# Driver_Adapter.net
KiCad netlist of a schematic drawn in EAGLE
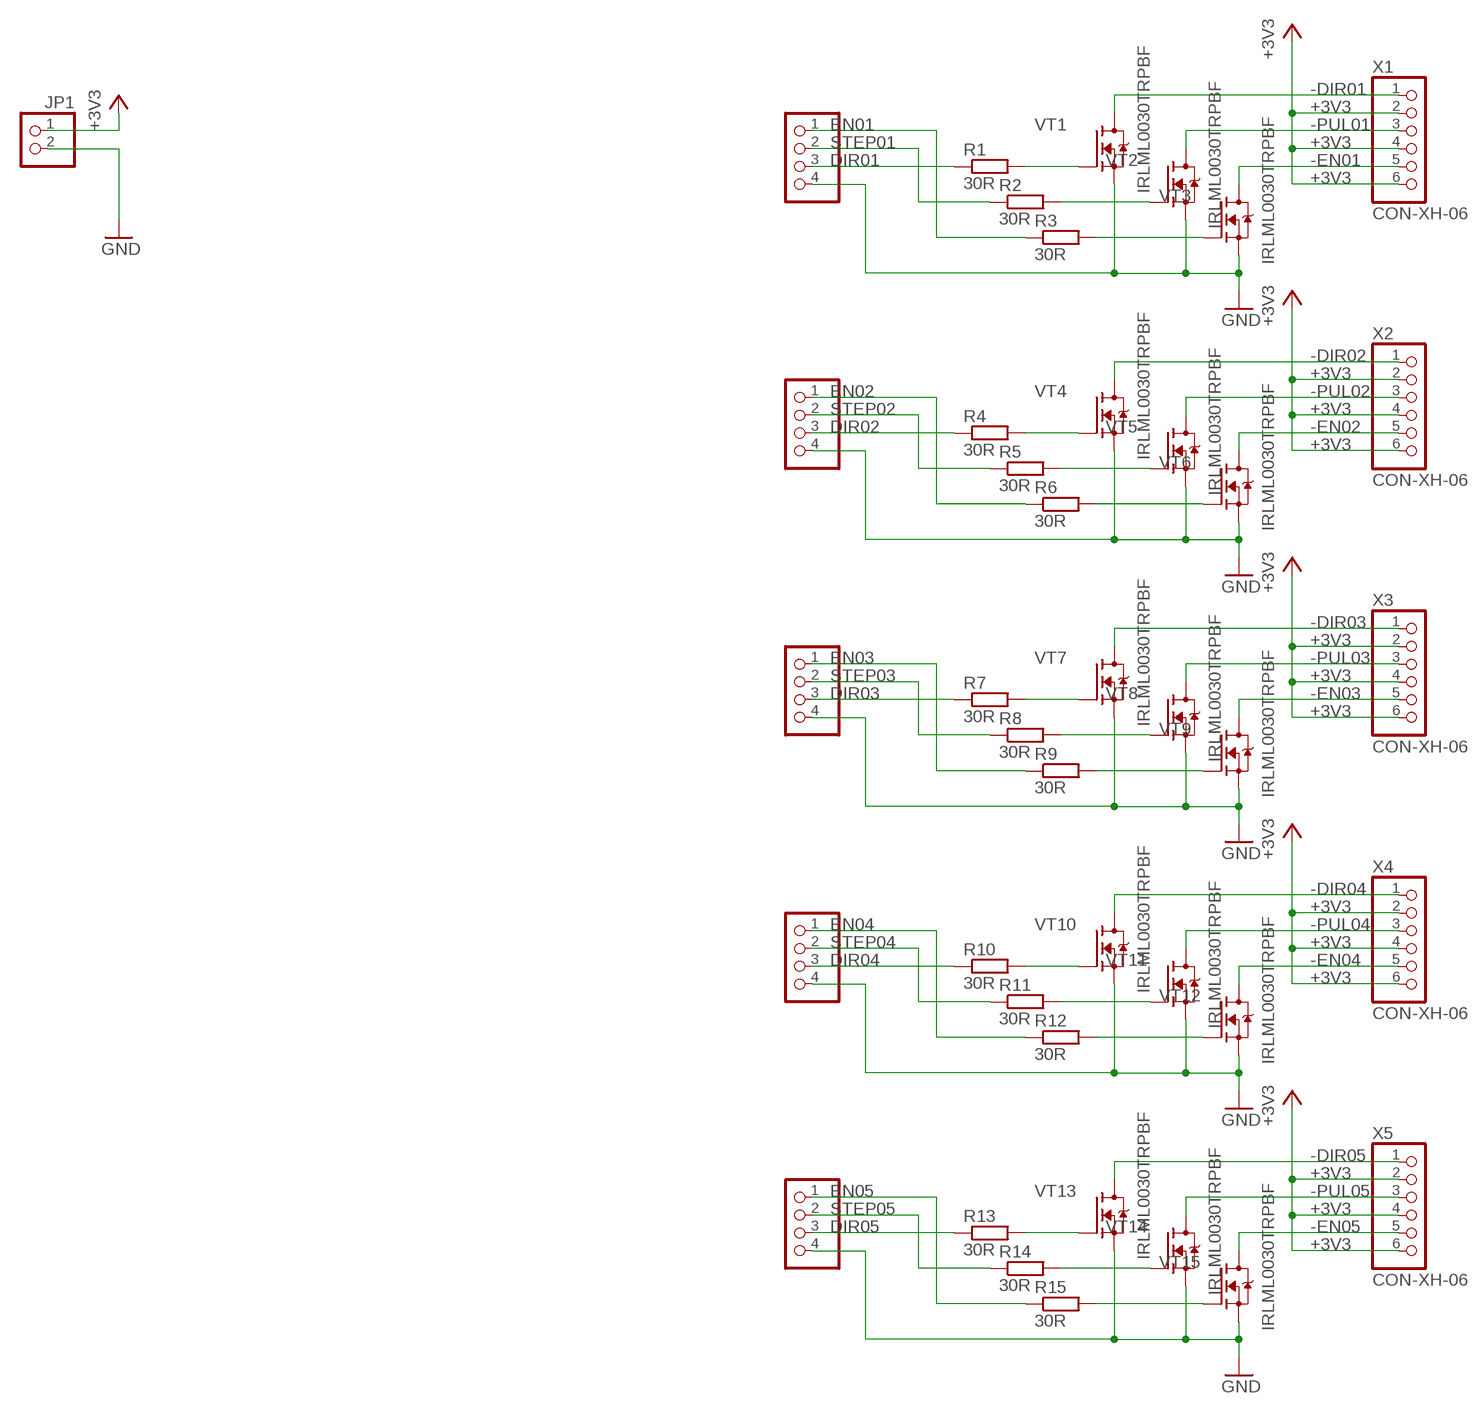
[diagram p0: schematic, sheet 1]

(export (version "E")
  (design (tool "Eeschema 10.0.6"))
  (components
    (comp (ref "JP1")
      (value "PINHD-1X2")
      (footprint "eagle-import:1X02")
      (libsource (lib "eagle-import") (part "PINHD-1X2"))
    )
    (comp (ref "JP2")
      (value "PINHD-1X4")
      (footprint "eagle-import:1X04")
      (libsource (lib "eagle-import") (part "PINHD-1X4"))
    )
    (comp (ref "JP3")
      (value "PINHD-1X4")
      (footprint "eagle-import:1X04")
      (libsource (lib "eagle-import") (part "PINHD-1X4"))
    )
    (comp (ref "JP4")
      (value "PINHD-1X4")
      (footprint "eagle-import:1X04")
      (libsource (lib "eagle-import") (part "PINHD-1X4"))
    )
    (comp (ref "JP5")
      (value "PINHD-1X4")
      (footprint "eagle-import:1X04")
      (libsource (lib "eagle-import") (part "PINHD-1X4"))
    )
    (comp (ref "JP6")
      (value "PINHD-1X4")
      (footprint "eagle-import:1X04")
      (libsource (lib "eagle-import") (part "PINHD-1X4"))
    )
    (comp (ref "R1")
      (value "30R")
      (footprint "eagle-import:RESC3216X60")
      (libsource (lib "eagle-import") (part "R_R1206"))
    )
    (comp (ref "R2")
      (value "30R")
      (footprint "eagle-import:RESC3216X60")
      (libsource (lib "eagle-import") (part "R_R1206"))
    )
    (comp (ref "R3")
      (value "30R")
      (footprint "eagle-import:RESC3216X60")
      (libsource (lib "eagle-import") (part "R_R1206"))
    )
    (comp (ref "R4")
      (value "30R")
      (footprint "eagle-import:RESC3216X60")
      (libsource (lib "eagle-import") (part "R_R1206"))
    )
    (comp (ref "R5")
      (value "30R")
      (footprint "eagle-import:RESC3216X60")
      (libsource (lib "eagle-import") (part "R_R1206"))
    )
    (comp (ref "R6")
      (value "30R")
      (footprint "eagle-import:RESC3216X60")
      (libsource (lib "eagle-import") (part "R_R1206"))
    )
    (comp (ref "R7")
      (value "30R")
      (footprint "eagle-import:RESC3216X60")
      (libsource (lib "eagle-import") (part "R_R1206"))
    )
    (comp (ref "R8")
      (value "30R")
      (footprint "eagle-import:RESC3216X60")
      (libsource (lib "eagle-import") (part "R_R1206"))
    )
    (comp (ref "R9")
      (value "30R")
      (footprint "eagle-import:RESC3216X60")
      (libsource (lib "eagle-import") (part "R_R1206"))
    )
    (comp (ref "R10")
      (value "30R")
      (footprint "eagle-import:RESC3216X60")
      (libsource (lib "eagle-import") (part "R_R1206"))
    )
    (comp (ref "R11")
      (value "30R")
      (footprint "eagle-import:RESC3216X60")
      (libsource (lib "eagle-import") (part "R_R1206"))
    )
    (comp (ref "R12")
      (value "30R")
      (footprint "eagle-import:RESC3216X60")
      (libsource (lib "eagle-import") (part "R_R1206"))
    )
    (comp (ref "R13")
      (value "30R")
      (footprint "eagle-import:RESC3216X60")
      (libsource (lib "eagle-import") (part "R_R1206"))
    )
    (comp (ref "R14")
      (value "30R")
      (footprint "eagle-import:RESC3216X60")
      (libsource (lib "eagle-import") (part "R_R1206"))
    )
    (comp (ref "R15")
      (value "30R")
      (footprint "eagle-import:RESC3216X60")
      (libsource (lib "eagle-import") (part "R_R1206"))
    )
    (comp (ref "VT1")
      (value "IRLML0030TRPBF")
      (footprint "eagle-import:SOT95P240X115-3")
      (libsource (lib "eagle-import") (part "FET-NSOT-23"))
    )
    (comp (ref "VT2")
      (value "IRLML0030TRPBF")
      (footprint "eagle-import:SOT95P240X115-3")
      (libsource (lib "eagle-import") (part "FET-NSOT-23"))
    )
    (comp (ref "VT3")
      (value "IRLML0030TRPBF")
      (footprint "eagle-import:SOT95P240X115-3")
      (libsource (lib "eagle-import") (part "FET-NSOT-23"))
    )
    (comp (ref "VT4")
      (value "IRLML0030TRPBF")
      (footprint "eagle-import:SOT95P240X115-3")
      (libsource (lib "eagle-import") (part "FET-NSOT-23"))
    )
    (comp (ref "VT5")
      (value "IRLML0030TRPBF")
      (footprint "eagle-import:SOT95P240X115-3")
      (libsource (lib "eagle-import") (part "FET-NSOT-23"))
    )
    (comp (ref "VT6")
      (value "IRLML0030TRPBF")
      (footprint "eagle-import:SOT95P240X115-3")
      (libsource (lib "eagle-import") (part "FET-NSOT-23"))
    )
    (comp (ref "VT7")
      (value "IRLML0030TRPBF")
      (footprint "eagle-import:SOT95P240X115-3")
      (libsource (lib "eagle-import") (part "FET-NSOT-23"))
    )
    (comp (ref "VT8")
      (value "IRLML0030TRPBF")
      (footprint "eagle-import:SOT95P240X115-3")
      (libsource (lib "eagle-import") (part "FET-NSOT-23"))
    )
    (comp (ref "VT9")
      (value "IRLML0030TRPBF")
      (footprint "eagle-import:SOT95P240X115-3")
      (libsource (lib "eagle-import") (part "FET-NSOT-23"))
    )
    (comp (ref "VT10")
      (value "IRLML0030TRPBF")
      (footprint "eagle-import:SOT95P240X115-3")
      (libsource (lib "eagle-import") (part "FET-NSOT-23"))
    )
    (comp (ref "VT11")
      (value "IRLML0030TRPBF")
      (footprint "eagle-import:SOT95P240X115-3")
      (libsource (lib "eagle-import") (part "FET-NSOT-23"))
    )
    (comp (ref "VT12")
      (value "IRLML0030TRPBF")
      (footprint "eagle-import:SOT95P240X115-3")
      (libsource (lib "eagle-import") (part "FET-NSOT-23"))
    )
    (comp (ref "VT13")
      (value "IRLML0030TRPBF")
      (footprint "eagle-import:SOT95P240X115-3")
      (libsource (lib "eagle-import") (part "FET-NSOT-23"))
    )
    (comp (ref "VT14")
      (value "IRLML0030TRPBF")
      (footprint "eagle-import:SOT95P240X115-3")
      (libsource (lib "eagle-import") (part "FET-NSOT-23"))
    )
    (comp (ref "VT15")
      (value "IRLML0030TRPBF")
      (footprint "eagle-import:SOT95P240X115-3")
      (libsource (lib "eagle-import") (part "FET-NSOT-23"))
    )
    (comp (ref "X1")
      (value "CON-XH-06")
      (footprint "eagle-import:XH-06")
      (libsource (lib "eagle-import") (part "CON-XH-06"))
    )
    (comp (ref "X2")
      (value "CON-XH-06")
      (footprint "eagle-import:XH-06")
      (libsource (lib "eagle-import") (part "CON-XH-06"))
    )
    (comp (ref "X3")
      (value "CON-XH-06")
      (footprint "eagle-import:XH-06")
      (libsource (lib "eagle-import") (part "CON-XH-06"))
    )
    (comp (ref "X4")
      (value "CON-XH-06")
      (footprint "eagle-import:XH-06")
      (libsource (lib "eagle-import") (part "CON-XH-06"))
    )
    (comp (ref "X5")
      (value "CON-XH-06")
      (footprint "eagle-import:XH-06")
      (libsource (lib "eagle-import") (part "CON-XH-06"))
    )
  )
  (nets
    (net (code "1") (name "+3V3") (class "Default")
      (node (ref "JP1") (pin "1") (pinfunction "1_1") (pintype "passive"))
      (node (ref "X1") (pin "2") (pinfunction "2_2") (pintype "passive"))
      (node (ref "X1") (pin "4") (pinfunction "4_4") (pintype "passive"))
      (node (ref "X1") (pin "6") (pinfunction "6_6") (pintype "passive"))
      (node (ref "X2") (pin "2") (pinfunction "2_2") (pintype "passive"))
      (node (ref "X2") (pin "4") (pinfunction "4_4") (pintype "passive"))
      (node (ref "X2") (pin "6") (pinfunction "6_6") (pintype "passive"))
      (node (ref "X3") (pin "2") (pinfunction "2_2") (pintype "passive"))
      (node (ref "X3") (pin "4") (pinfunction "4_4") (pintype "passive"))
      (node (ref "X3") (pin "6") (pinfunction "6_6") (pintype "passive"))
      (node (ref "X4") (pin "2") (pinfunction "2_2") (pintype "passive"))
      (node (ref "X4") (pin "4") (pinfunction "4_4") (pintype "passive"))
      (node (ref "X4") (pin "6") (pinfunction "6_6") (pintype "passive"))
      (node (ref "X5") (pin "2") (pinfunction "2_2") (pintype "passive"))
      (node (ref "X5") (pin "4") (pinfunction "4_4") (pintype "passive"))
      (node (ref "X5") (pin "6") (pinfunction "6_6") (pintype "passive"))
    )
    (net (code "2") (name "/-DIR01") (class "Default")
      (node (ref "VT1") (pin "3") (pinfunction "D_3") (pintype "passive"))
      (node (ref "X1") (pin "1") (pinfunction "1_1") (pintype "passive"))
    )
    (net (code "3") (name "/-DIR02") (class "Default")
      (node (ref "VT4") (pin "3") (pinfunction "D_3") (pintype "passive"))
      (node (ref "X2") (pin "1") (pinfunction "1_1") (pintype "passive"))
    )
    (net (code "4") (name "/-DIR03") (class "Default")
      (node (ref "VT7") (pin "3") (pinfunction "D_3") (pintype "passive"))
      (node (ref "X3") (pin "1") (pinfunction "1_1") (pintype "passive"))
    )
    (net (code "5") (name "/-DIR04") (class "Default")
      (node (ref "VT10") (pin "3") (pinfunction "D_3") (pintype "passive"))
      (node (ref "X4") (pin "1") (pinfunction "1_1") (pintype "passive"))
    )
    (net (code "6") (name "/-DIR05") (class "Default")
      (node (ref "VT13") (pin "3") (pinfunction "D_3") (pintype "passive"))
      (node (ref "X5") (pin "1") (pinfunction "1_1") (pintype "passive"))
    )
    (net (code "7") (name "/-EN01") (class "Default")
      (node (ref "VT3") (pin "3") (pinfunction "D_3") (pintype "passive"))
      (node (ref "X1") (pin "5") (pinfunction "5_5") (pintype "passive"))
    )
    (net (code "8") (name "/-EN02") (class "Default")
      (node (ref "VT6") (pin "3") (pinfunction "D_3") (pintype "passive"))
      (node (ref "X2") (pin "5") (pinfunction "5_5") (pintype "passive"))
    )
    (net (code "9") (name "/-EN03") (class "Default")
      (node (ref "VT9") (pin "3") (pinfunction "D_3") (pintype "passive"))
      (node (ref "X3") (pin "5") (pinfunction "5_5") (pintype "passive"))
    )
    (net (code "10") (name "/-EN04") (class "Default")
      (node (ref "VT12") (pin "3") (pinfunction "D_3") (pintype "passive"))
      (node (ref "X4") (pin "5") (pinfunction "5_5") (pintype "passive"))
    )
    (net (code "11") (name "/-EN05") (class "Default")
      (node (ref "VT15") (pin "3") (pinfunction "D_3") (pintype "passive"))
      (node (ref "X5") (pin "5") (pinfunction "5_5") (pintype "passive"))
    )
    (net (code "12") (name "/-PUL01") (class "Default")
      (node (ref "VT2") (pin "3") (pinfunction "D_3") (pintype "passive"))
      (node (ref "X1") (pin "3") (pinfunction "3_3") (pintype "passive"))
    )
    (net (code "13") (name "/-PUL02") (class "Default")
      (node (ref "VT5") (pin "3") (pinfunction "D_3") (pintype "passive"))
      (node (ref "X2") (pin "3") (pinfunction "3_3") (pintype "passive"))
    )
    (net (code "14") (name "/-PUL03") (class "Default")
      (node (ref "VT8") (pin "3") (pinfunction "D_3") (pintype "passive"))
      (node (ref "X3") (pin "3") (pinfunction "3_3") (pintype "passive"))
    )
    (net (code "15") (name "/-PUL04") (class "Default")
      (node (ref "VT11") (pin "3") (pinfunction "D_3") (pintype "passive"))
      (node (ref "X4") (pin "3") (pinfunction "3_3") (pintype "passive"))
    )
    (net (code "16") (name "/-PUL05") (class "Default")
      (node (ref "VT14") (pin "3") (pinfunction "D_3") (pintype "passive"))
      (node (ref "X5") (pin "3") (pinfunction "3_3") (pintype "passive"))
    )
    (net (code "17") (name "/DIR01") (class "Default")
      (node (ref "JP2") (pin "3") (pinfunction "3_3") (pintype "passive"))
      (node (ref "R1") (pin "1") (pinfunction "1_1") (pintype "passive"))
    )
    (net (code "18") (name "/DIR02") (class "Default")
      (node (ref "JP3") (pin "3") (pinfunction "3_3") (pintype "passive"))
      (node (ref "R4") (pin "1") (pinfunction "1_1") (pintype "passive"))
    )
    (net (code "19") (name "/DIR03") (class "Default")
      (node (ref "JP4") (pin "3") (pinfunction "3_3") (pintype "passive"))
      (node (ref "R7") (pin "1") (pinfunction "1_1") (pintype "passive"))
    )
    (net (code "20") (name "/DIR04") (class "Default")
      (node (ref "JP5") (pin "3") (pinfunction "3_3") (pintype "passive"))
      (node (ref "R10") (pin "1") (pinfunction "1_1") (pintype "passive"))
    )
    (net (code "21") (name "/DIR05") (class "Default")
      (node (ref "JP6") (pin "3") (pinfunction "3_3") (pintype "passive"))
      (node (ref "R13") (pin "1") (pinfunction "1_1") (pintype "passive"))
    )
    (net (code "22") (name "/EN01") (class "Default")
      (node (ref "JP2") (pin "1") (pinfunction "1_1") (pintype "passive"))
      (node (ref "R3") (pin "1") (pinfunction "1_1") (pintype "passive"))
    )
    (net (code "23") (name "/EN02") (class "Default")
      (node (ref "JP3") (pin "1") (pinfunction "1_1") (pintype "passive"))
      (node (ref "R6") (pin "1") (pinfunction "1_1") (pintype "passive"))
    )
    (net (code "24") (name "/EN03") (class "Default")
      (node (ref "JP4") (pin "1") (pinfunction "1_1") (pintype "passive"))
      (node (ref "R9") (pin "1") (pinfunction "1_1") (pintype "passive"))
    )
    (net (code "25") (name "/EN04") (class "Default")
      (node (ref "JP5") (pin "1") (pinfunction "1_1") (pintype "passive"))
      (node (ref "R12") (pin "1") (pinfunction "1_1") (pintype "passive"))
    )
    (net (code "26") (name "/EN05") (class "Default")
      (node (ref "JP6") (pin "1") (pinfunction "1_1") (pintype "passive"))
      (node (ref "R15") (pin "1") (pinfunction "1_1") (pintype "passive"))
    )
    (net (code "27") (name "/STEP01") (class "Default")
      (node (ref "JP2") (pin "2") (pinfunction "2_2") (pintype "passive"))
      (node (ref "R2") (pin "1") (pinfunction "1_1") (pintype "passive"))
    )
    (net (code "28") (name "/STEP02") (class "Default")
      (node (ref "JP3") (pin "2") (pinfunction "2_2") (pintype "passive"))
      (node (ref "R5") (pin "1") (pinfunction "1_1") (pintype "passive"))
    )
    (net (code "29") (name "/STEP03") (class "Default")
      (node (ref "JP4") (pin "2") (pinfunction "2_2") (pintype "passive"))
      (node (ref "R8") (pin "1") (pinfunction "1_1") (pintype "passive"))
    )
    (net (code "30") (name "/STEP04") (class "Default")
      (node (ref "JP5") (pin "2") (pinfunction "2_2") (pintype "passive"))
      (node (ref "R11") (pin "1") (pinfunction "1_1") (pintype "passive"))
    )
    (net (code "31") (name "/STEP05") (class "Default")
      (node (ref "JP6") (pin "2") (pinfunction "2_2") (pintype "passive"))
      (node (ref "R14") (pin "1") (pinfunction "1_1") (pintype "passive"))
    )
    (net (code "32") (name "GND") (class "Default")
      (node (ref "JP1") (pin "2") (pinfunction "2_2") (pintype "passive"))
      (node (ref "JP2") (pin "4") (pinfunction "4_4") (pintype "passive"))
      (node (ref "JP3") (pin "4") (pinfunction "4_4") (pintype "passive"))
      (node (ref "JP4") (pin "4") (pinfunction "4_4") (pintype "passive"))
      (node (ref "JP5") (pin "4") (pinfunction "4_4") (pintype "passive"))
      (node (ref "JP6") (pin "4") (pinfunction "4_4") (pintype "passive"))
      (node (ref "VT1") (pin "2") (pinfunction "S_2") (pintype "passive"))
      (node (ref "VT10") (pin "2") (pinfunction "S_2") (pintype "passive"))
      (node (ref "VT11") (pin "2") (pinfunction "S_2") (pintype "passive"))
      (node (ref "VT12") (pin "2") (pinfunction "S_2") (pintype "passive"))
      (node (ref "VT13") (pin "2") (pinfunction "S_2") (pintype "passive"))
      (node (ref "VT14") (pin "2") (pinfunction "S_2") (pintype "passive"))
      (node (ref "VT15") (pin "2") (pinfunction "S_2") (pintype "passive"))
      (node (ref "VT2") (pin "2") (pinfunction "S_2") (pintype "passive"))
      (node (ref "VT3") (pin "2") (pinfunction "S_2") (pintype "passive"))
      (node (ref "VT4") (pin "2") (pinfunction "S_2") (pintype "passive"))
      (node (ref "VT5") (pin "2") (pinfunction "S_2") (pintype "passive"))
      (node (ref "VT6") (pin "2") (pinfunction "S_2") (pintype "passive"))
      (node (ref "VT7") (pin "2") (pinfunction "S_2") (pintype "passive"))
      (node (ref "VT8") (pin "2") (pinfunction "S_2") (pintype "passive"))
      (node (ref "VT9") (pin "2") (pinfunction "S_2") (pintype "passive"))
    )
    (net (code "33") (name "Net-(VT1-G)") (class "Default")
      (node (ref "R1") (pin "2") (pinfunction "2_2") (pintype "passive"))
      (node (ref "VT1") (pin "1") (pinfunction "G_1") (pintype "passive"))
    )
    (net (code "34") (name "Net-(VT2-G)") (class "Default")
      (node (ref "R2") (pin "2") (pinfunction "2_2") (pintype "passive"))
      (node (ref "VT2") (pin "1") (pinfunction "G_1") (pintype "passive"))
    )
    (net (code "35") (name "Net-(VT3-G)") (class "Default")
      (node (ref "R3") (pin "2") (pinfunction "2_2") (pintype "passive"))
      (node (ref "VT3") (pin "1") (pinfunction "G_1") (pintype "passive"))
    )
    (net (code "36") (name "Net-(VT4-G)") (class "Default")
      (node (ref "R4") (pin "2") (pinfunction "2_2") (pintype "passive"))
      (node (ref "VT4") (pin "1") (pinfunction "G_1") (pintype "passive"))
    )
    (net (code "37") (name "Net-(VT5-G)") (class "Default")
      (node (ref "R5") (pin "2") (pinfunction "2_2") (pintype "passive"))
      (node (ref "VT5") (pin "1") (pinfunction "G_1") (pintype "passive"))
    )
    (net (code "38") (name "Net-(VT6-G)") (class "Default")
      (node (ref "R6") (pin "2") (pinfunction "2_2") (pintype "passive"))
      (node (ref "VT6") (pin "1") (pinfunction "G_1") (pintype "passive"))
    )
    (net (code "39") (name "Net-(VT7-G)") (class "Default")
      (node (ref "R7") (pin "2") (pinfunction "2_2") (pintype "passive"))
      (node (ref "VT7") (pin "1") (pinfunction "G_1") (pintype "passive"))
    )
    (net (code "40") (name "Net-(VT8-G)") (class "Default")
      (node (ref "R8") (pin "2") (pinfunction "2_2") (pintype "passive"))
      (node (ref "VT8") (pin "1") (pinfunction "G_1") (pintype "passive"))
    )
    (net (code "41") (name "Net-(VT9-G)") (class "Default")
      (node (ref "R9") (pin "2") (pinfunction "2_2") (pintype "passive"))
      (node (ref "VT9") (pin "1") (pinfunction "G_1") (pintype "passive"))
    )
    (net (code "42") (name "Net-(VT10-G)") (class "Default")
      (node (ref "R10") (pin "2") (pinfunction "2_2") (pintype "passive"))
      (node (ref "VT10") (pin "1") (pinfunction "G_1") (pintype "passive"))
    )
    (net (code "43") (name "Net-(VT11-G)") (class "Default")
      (node (ref "R11") (pin "2") (pinfunction "2_2") (pintype "passive"))
      (node (ref "VT11") (pin "1") (pinfunction "G_1") (pintype "passive"))
    )
    (net (code "44") (name "Net-(VT12-G)") (class "Default")
      (node (ref "R12") (pin "2") (pinfunction "2_2") (pintype "passive"))
      (node (ref "VT12") (pin "1") (pinfunction "G_1") (pintype "passive"))
    )
    (net (code "45") (name "Net-(VT13-G)") (class "Default")
      (node (ref "R13") (pin "2") (pinfunction "2_2") (pintype "passive"))
      (node (ref "VT13") (pin "1") (pinfunction "G_1") (pintype "passive"))
    )
    (net (code "46") (name "Net-(VT14-G)") (class "Default")
      (node (ref "R14") (pin "2") (pinfunction "2_2") (pintype "passive"))
      (node (ref "VT14") (pin "1") (pinfunction "G_1") (pintype "passive"))
    )
    (net (code "47") (name "Net-(VT15-G)") (class "Default")
      (node (ref "R15") (pin "2") (pinfunction "2_2") (pintype "passive"))
      (node (ref "VT15") (pin "1") (pinfunction "G_1") (pintype "passive"))
    )
  )
)
